# sc-001.net
KiCad netlist of a schematic drawn in EAGLE
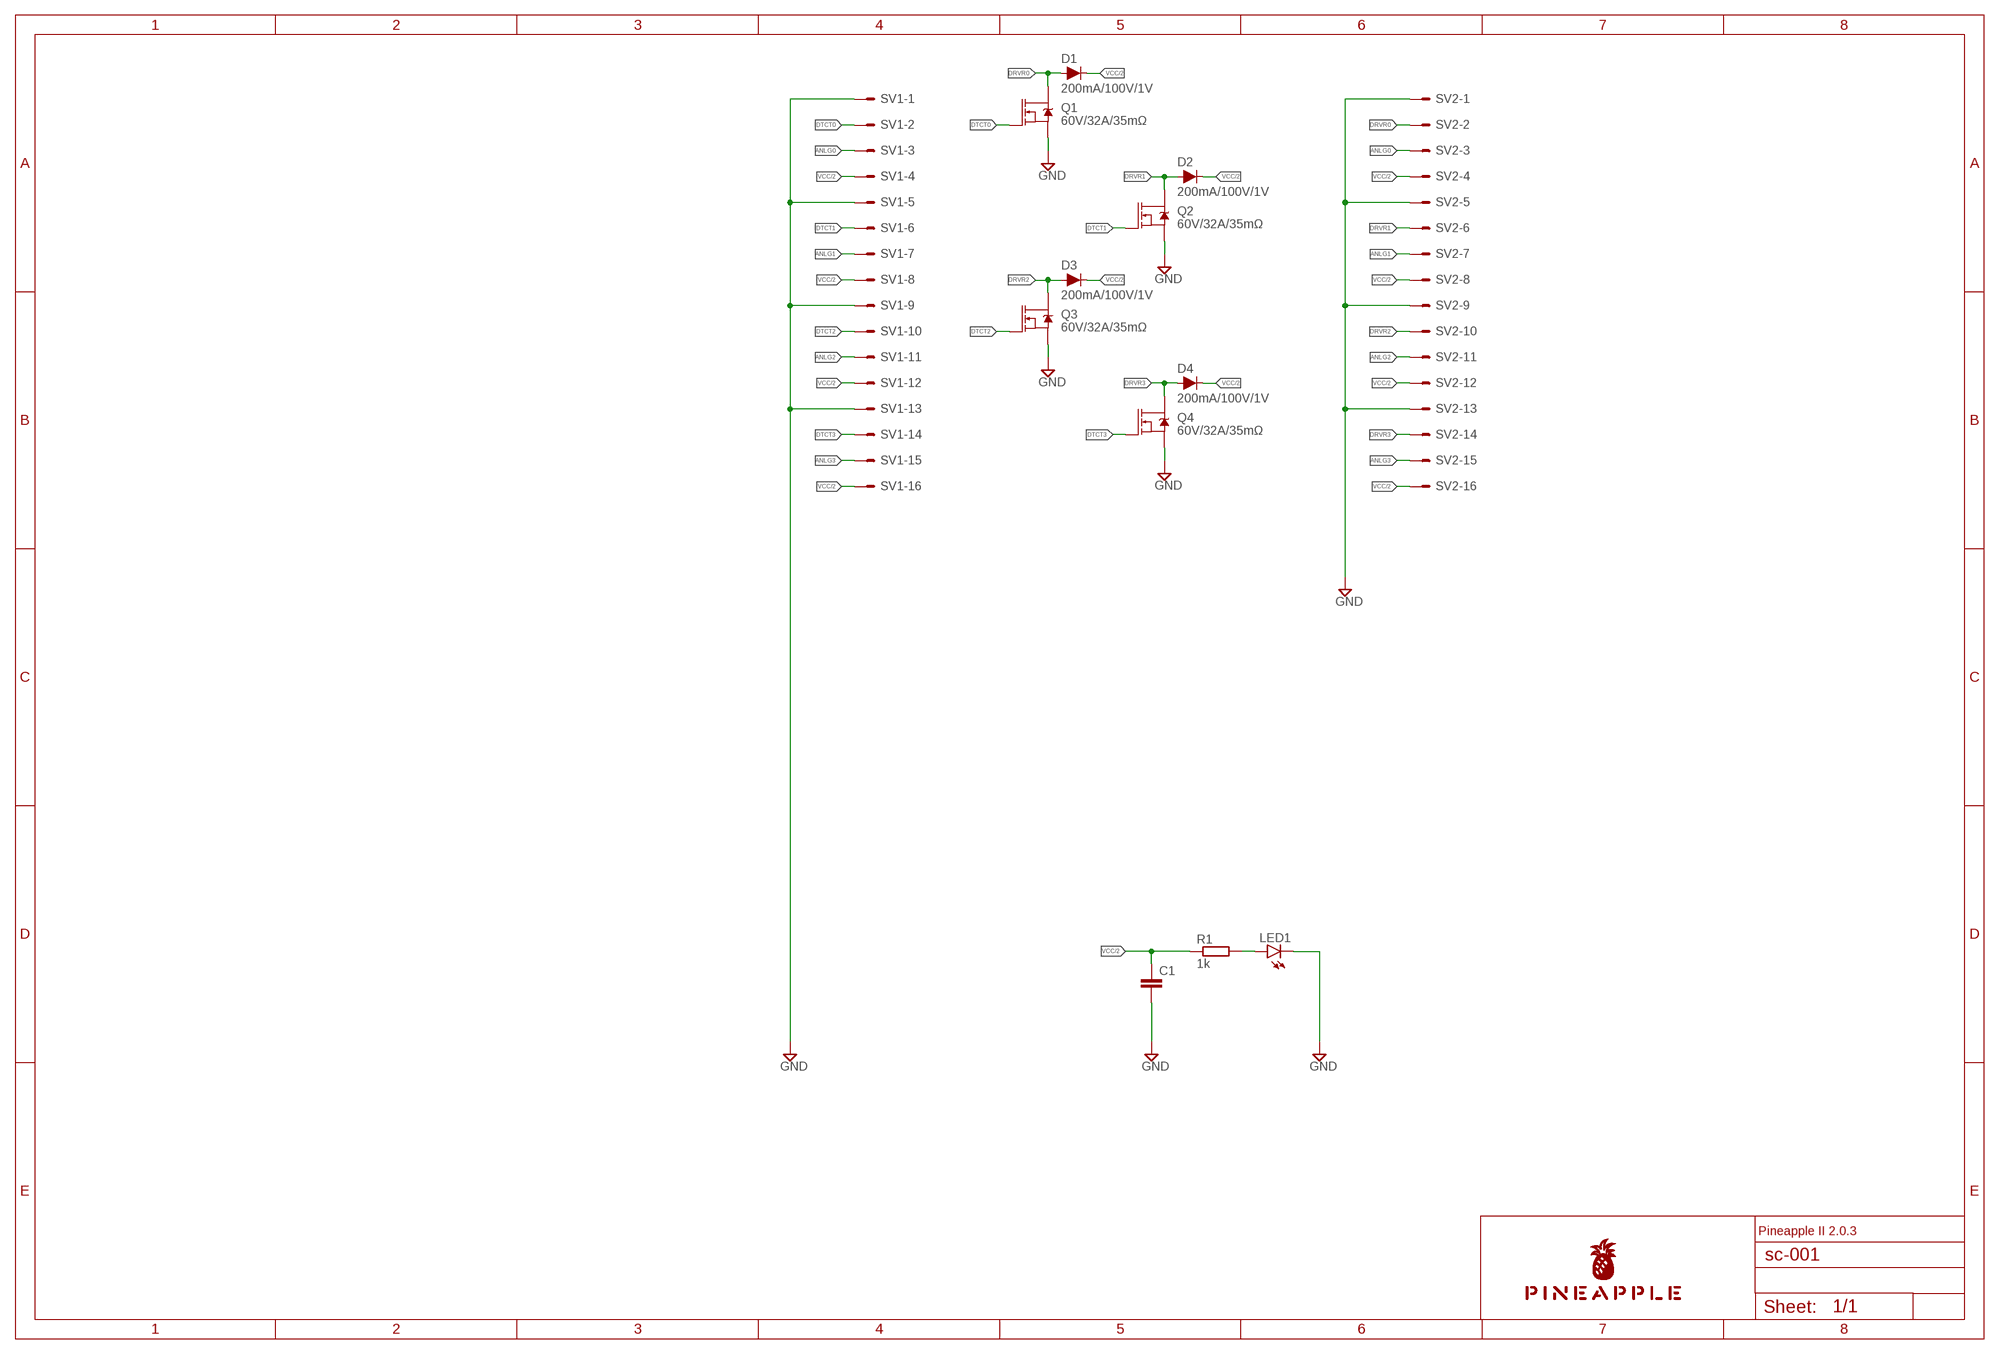
[diagram p0: schematic, sheet 1]

(export (version "E")
  (design (tool "Eeschema 10.0.6"))
  (components
    (comp (ref "C1")
      (value "C-EU025-025X050")
      (footprint "eagle-import:C025-025X050")
      (libsource (lib "eagle-import") (part "C-EU025-025X050"))
    )
    (comp (ref "D1")
      (value "200mA/100V/1V")
      (footprint "eagle-import:DIODE-1N4148")
      (libsource (lib "eagle-import") (part "DIODE-1N4148"))
    )
    (comp (ref "D2")
      (value "200mA/100V/1V")
      (footprint "eagle-import:DIODE-1N4148")
      (libsource (lib "eagle-import") (part "DIODE-1N4148"))
    )
    (comp (ref "D3")
      (value "200mA/100V/1V")
      (footprint "eagle-import:DIODE-1N4148")
      (libsource (lib "eagle-import") (part "DIODE-1N4148"))
    )
    (comp (ref "D4")
      (value "200mA/100V/1V")
      (footprint "eagle-import:DIODE-1N4148")
      (libsource (lib "eagle-import") (part "DIODE-1N4148"))
    )
    (comp (ref "LED1")
      (value "LED3MM")
      (footprint "eagle-import:LED3MM")
      (libsource (lib "eagle-import") (part "LED3MM"))
    )
    (comp (ref "Q1")
      (value "60V/32A/35mΩ")
      (footprint "eagle-import:TO220V")
      (libsource (lib "eagle-import") (part "MOSFET-NCH-FQP30N06L"))
    )
    (comp (ref "Q2")
      (value "60V/32A/35mΩ")
      (footprint "eagle-import:TO220V")
      (libsource (lib "eagle-import") (part "MOSFET-NCH-FQP30N06L"))
    )
    (comp (ref "Q3")
      (value "60V/32A/35mΩ")
      (footprint "eagle-import:TO220V")
      (libsource (lib "eagle-import") (part "MOSFET-NCH-FQP30N06L"))
    )
    (comp (ref "Q4")
      (value "60V/32A/35mΩ")
      (footprint "eagle-import:TO220V")
      (libsource (lib "eagle-import") (part "MOSFET-NCH-FQP30N06L"))
    )
    (comp (ref "R1")
      (value "1k")
      (footprint "eagle-import:0204_5")
      (libsource (lib "eagle-import") (part "R-EU_0204/5"))
    )
    (comp (ref "SV1")
      (value "ML16LE")
      (footprint "eagle-import:ML16L")
      (libsource (lib "eagle-import") (part "ML16LE"))
    )
    (comp (ref "SV2")
      (value "ML16LE")
      (footprint "eagle-import:ML16L")
      (libsource (lib "eagle-import") (part "ML16LE"))
    )
    (comp (ref "U$1")
      (value "PINEAPPLE450_SILK")
      (footprint "eagle-import:PINEAPPLE450_SILK")
      (libsource (lib "eagle-import") (part "PINEAPPLE450_SILK"))
    )
  )
  (nets
    (net (code "1") (name "ANLG0") (class "Default")
      (node (ref "SV1") (pin "3") (pinfunction "S_3") (pintype "passive"))
      (node (ref "SV2") (pin "3") (pinfunction "S_3") (pintype "passive"))
    )
    (net (code "2") (name "ANLG1") (class "Default")
      (node (ref "SV1") (pin "7") (pinfunction "S_7") (pintype "passive"))
      (node (ref "SV2") (pin "7") (pinfunction "S_7") (pintype "passive"))
    )
    (net (code "3") (name "ANLG2") (class "Default")
      (node (ref "SV1") (pin "11") (pinfunction "S_11") (pintype "passive"))
      (node (ref "SV2") (pin "11") (pinfunction "S_11") (pintype "passive"))
    )
    (net (code "4") (name "ANLG3") (class "Default")
      (node (ref "SV1") (pin "15") (pinfunction "S_15") (pintype "passive"))
      (node (ref "SV2") (pin "15") (pinfunction "S_15") (pintype "passive"))
    )
    (net (code "5") (name "DRVR0") (class "Default")
      (node (ref "D1") (pin "A") (pinfunction "A_A") (pintype "passive"))
      (node (ref "Q1") (pin "2") (pinfunction "D_2") (pintype "bidirectional"))
      (node (ref "SV2") (pin "2") (pinfunction "S_2") (pintype "passive"))
    )
    (net (code "6") (name "DRVR1") (class "Default")
      (node (ref "D2") (pin "A") (pinfunction "A_A") (pintype "passive"))
      (node (ref "Q2") (pin "2") (pinfunction "D_2") (pintype "bidirectional"))
      (node (ref "SV2") (pin "6") (pinfunction "S_6") (pintype "passive"))
    )
    (net (code "7") (name "DRVR2") (class "Default")
      (node (ref "D3") (pin "A") (pinfunction "A_A") (pintype "passive"))
      (node (ref "Q3") (pin "2") (pinfunction "D_2") (pintype "bidirectional"))
      (node (ref "SV2") (pin "10") (pinfunction "S_10") (pintype "passive"))
    )
    (net (code "8") (name "DRVR3") (class "Default")
      (node (ref "D4") (pin "A") (pinfunction "A_A") (pintype "passive"))
      (node (ref "Q4") (pin "2") (pinfunction "D_2") (pintype "bidirectional"))
      (node (ref "SV2") (pin "14") (pinfunction "S_14") (pintype "passive"))
    )
    (net (code "9") (name "DTCT0") (class "Default")
      (node (ref "Q1") (pin "1") (pinfunction "G_1") (pintype "bidirectional"))
      (node (ref "SV1") (pin "2") (pinfunction "S_2") (pintype "passive"))
    )
    (net (code "10") (name "DTCT1") (class "Default")
      (node (ref "Q2") (pin "1") (pinfunction "G_1") (pintype "bidirectional"))
      (node (ref "SV1") (pin "6") (pinfunction "S_6") (pintype "passive"))
    )
    (net (code "11") (name "DTCT2") (class "Default")
      (node (ref "Q3") (pin "1") (pinfunction "G_1") (pintype "bidirectional"))
      (node (ref "SV1") (pin "10") (pinfunction "S_10") (pintype "passive"))
    )
    (net (code "12") (name "DTCT3") (class "Default")
      (node (ref "Q4") (pin "1") (pinfunction "G_1") (pintype "bidirectional"))
      (node (ref "SV1") (pin "14") (pinfunction "S_14") (pintype "passive"))
    )
    (net (code "13") (name "GND") (class "Default")
      (node (ref "C1") (pin "2") (pinfunction "2_2") (pintype "passive"))
      (node (ref "LED1") (pin "K") (pinfunction "C_K") (pintype "passive"))
      (node (ref "Q1") (pin "3") (pinfunction "S_3") (pintype "bidirectional"))
      (node (ref "Q2") (pin "3") (pinfunction "S_3") (pintype "bidirectional"))
      (node (ref "Q3") (pin "3") (pinfunction "S_3") (pintype "bidirectional"))
      (node (ref "Q4") (pin "3") (pinfunction "S_3") (pintype "bidirectional"))
      (node (ref "SV1") (pin "1") (pinfunction "S_1") (pintype "passive"))
      (node (ref "SV1") (pin "13") (pinfunction "S_13") (pintype "passive"))
      (node (ref "SV1") (pin "5") (pinfunction "S_5") (pintype "passive"))
      (node (ref "SV1") (pin "9") (pinfunction "S_9") (pintype "passive"))
      (node (ref "SV2") (pin "1") (pinfunction "S_1") (pintype "passive"))
      (node (ref "SV2") (pin "13") (pinfunction "S_13") (pintype "passive"))
      (node (ref "SV2") (pin "5") (pinfunction "S_5") (pintype "passive"))
      (node (ref "SV2") (pin "9") (pinfunction "S_9") (pintype "passive"))
    )
    (net (code "14") (name "Net-(LED1-PadA)") (class "Default")
      (node (ref "LED1") (pin "A") (pinfunction "A_A") (pintype "passive"))
      (node (ref "R1") (pin "2") (pinfunction "2_2") (pintype "passive"))
    )
    (net (code "15") (name "VCC{slash}2") (class "Default")
      (node (ref "C1") (pin "1") (pinfunction "1_1") (pintype "passive"))
      (node (ref "D1") (pin "C") (pinfunction "C_C") (pintype "passive"))
      (node (ref "D2") (pin "C") (pinfunction "C_C") (pintype "passive"))
      (node (ref "D3") (pin "C") (pinfunction "C_C") (pintype "passive"))
      (node (ref "D4") (pin "C") (pinfunction "C_C") (pintype "passive"))
      (node (ref "R1") (pin "1") (pinfunction "1_1") (pintype "passive"))
      (node (ref "SV1") (pin "12") (pinfunction "S_12") (pintype "passive"))
      (node (ref "SV1") (pin "16") (pinfunction "S_16") (pintype "passive"))
      (node (ref "SV1") (pin "4") (pinfunction "S_4") (pintype "passive"))
      (node (ref "SV1") (pin "8") (pinfunction "S_8") (pintype "passive"))
      (node (ref "SV2") (pin "12") (pinfunction "S_12") (pintype "passive"))
      (node (ref "SV2") (pin "16") (pinfunction "S_16") (pintype "passive"))
      (node (ref "SV2") (pin "4") (pinfunction "S_4") (pintype "passive"))
      (node (ref "SV2") (pin "8") (pinfunction "S_8") (pintype "passive"))
    )
  )
)
